# Callisto_Teknic_MSO_PBx4_v1p0.net
KiCad netlist of a schematic drawn in EAGLE
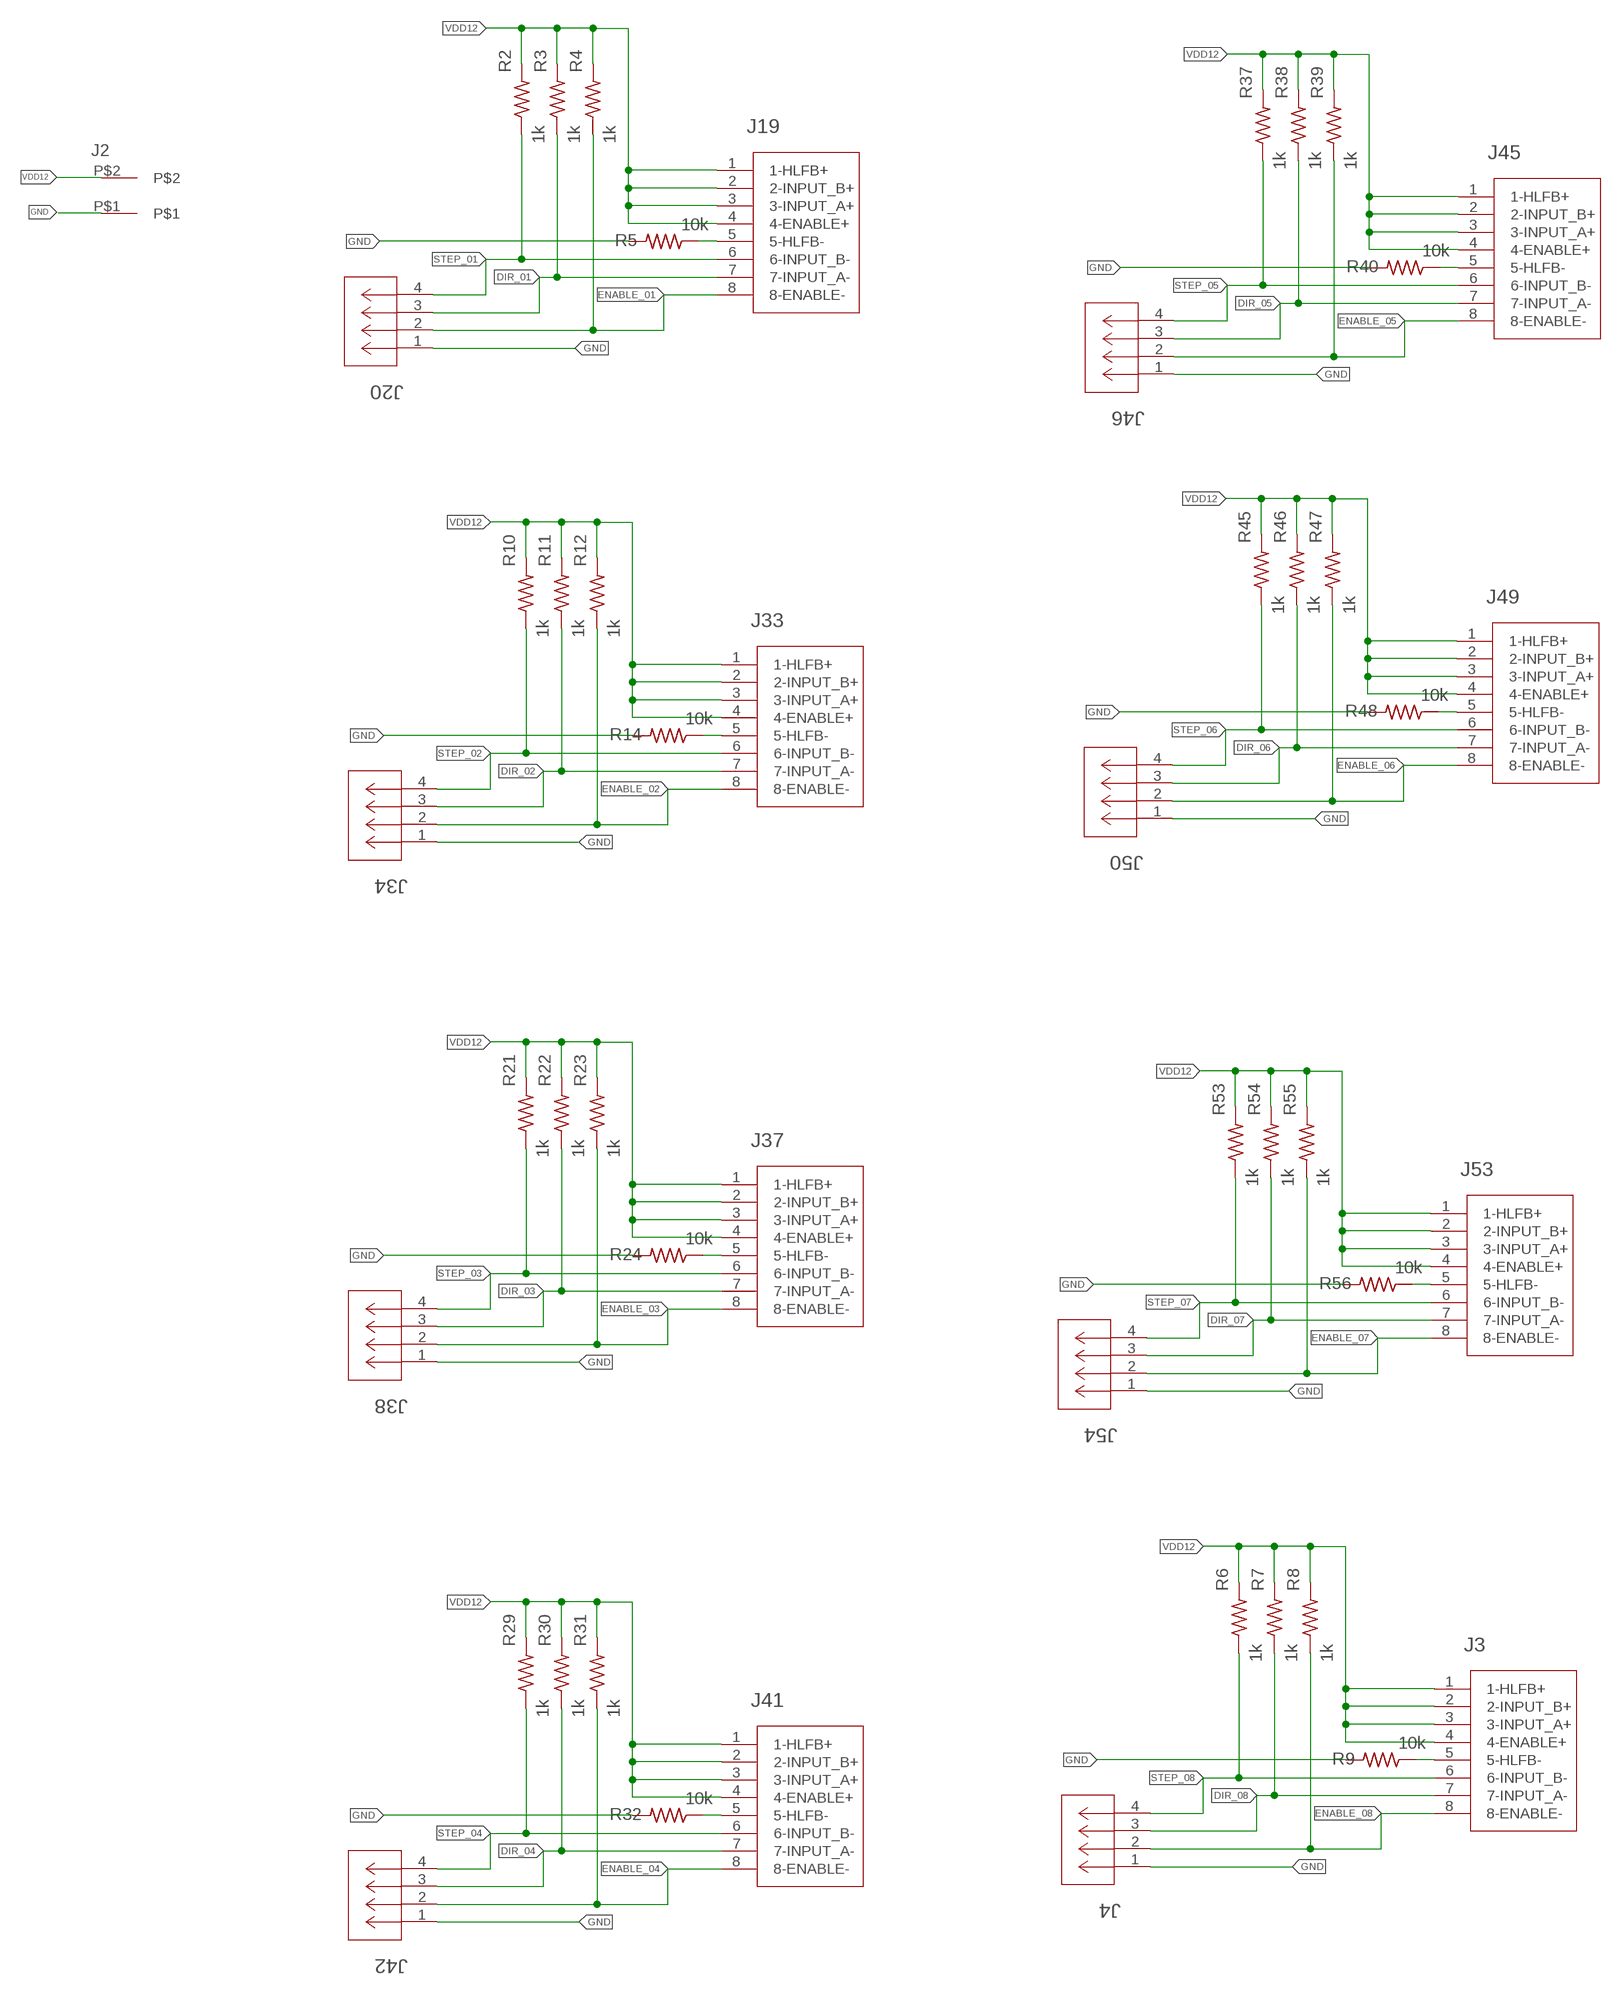
[diagram p0: schematic, sheet 1]

(export (version "E")
  (design (tool "Eeschema 10.0.6"))
  (components
    (comp (ref "J2")
      (value "2-pos")
      (footprint "eagle-import:2_3.81MM_PITCH")
      (fields (field (name "PARTNO") "691322310002"))
      (libsource (lib "eagle-import") (part "3.81MM_1_X_2_RT_ANGLE_PLUG_HEADER"))
    )
    (comp (ref "J3")
      (value "TEKNIC_8PIN_MOTOR")
      (footprint "eagle-import:CON_39281083")
      (fields
        (field (name "MANUFACTURER_PART_NUMBER") "39281083")
        (field (name "COPYRIGHT") "Copyright (C) 2022 Ultra Librarian. All rights reserved.")
      )
      (libsource (lib "eagle-import") (part "TEKNIC_8PIN_MOTOR"))
    )
    (comp (ref "J4")
      (value "CONN_530470410_PICOBLADE_X_4")
      (footprint "eagle-import:CON_530470410_MOL")
      (fields
        (field (name "MANUFACTURER_PART_NUMBER") "530470410")
        (field (name "COPYRIGHT") "Copyright (C) 2022 Ultra Librarian. All rights reserved.")
      )
      (libsource (lib "eagle-import") (part "CONN_530470410_PICOBLADE_X_4"))
    )
    (comp (ref "J19")
      (value "TEKNIC_8PIN_MOTOR")
      (footprint "eagle-import:CON_39281083")
      (fields
        (field (name "MANUFACTURER_PART_NUMBER") "39281083")
        (field (name "COPYRIGHT") "Copyright (C) 2022 Ultra Librarian. All rights reserved.")
      )
      (libsource (lib "eagle-import") (part "TEKNIC_8PIN_MOTOR"))
    )
    (comp (ref "J20")
      (value "CONN_530470410_PICOBLADE_X_4")
      (footprint "eagle-import:CON_530470410_MOL")
      (fields
        (field (name "MANUFACTURER_PART_NUMBER") "530470410")
        (field (name "COPYRIGHT") "Copyright (C) 2022 Ultra Librarian. All rights reserved.")
      )
      (libsource (lib "eagle-import") (part "CONN_530470410_PICOBLADE_X_4"))
    )
    (comp (ref "J33")
      (value "TEKNIC_8PIN_MOTOR")
      (footprint "eagle-import:CON_39281083")
      (fields
        (field (name "MANUFACTURER_PART_NUMBER") "39281083")
        (field (name "COPYRIGHT") "Copyright (C) 2022 Ultra Librarian. All rights reserved.")
      )
      (libsource (lib "eagle-import") (part "TEKNIC_8PIN_MOTOR"))
    )
    (comp (ref "J34")
      (value "CONN_530470410_PICOBLADE_X_4")
      (footprint "eagle-import:CON_530470410_MOL")
      (fields
        (field (name "MANUFACTURER_PART_NUMBER") "530470410")
        (field (name "COPYRIGHT") "Copyright (C) 2022 Ultra Librarian. All rights reserved.")
      )
      (libsource (lib "eagle-import") (part "CONN_530470410_PICOBLADE_X_4"))
    )
    (comp (ref "J37")
      (value "TEKNIC_8PIN_MOTOR")
      (footprint "eagle-import:CON_39281083")
      (fields
        (field (name "MANUFACTURER_PART_NUMBER") "39281083")
        (field (name "COPYRIGHT") "Copyright (C) 2022 Ultra Librarian. All rights reserved.")
      )
      (libsource (lib "eagle-import") (part "TEKNIC_8PIN_MOTOR"))
    )
    (comp (ref "J38")
      (value "CONN_530470410_PICOBLADE_X_4")
      (footprint "eagle-import:CON_530470410_MOL")
      (fields
        (field (name "MANUFACTURER_PART_NUMBER") "530470410")
        (field (name "COPYRIGHT") "Copyright (C) 2022 Ultra Librarian. All rights reserved.")
      )
      (libsource (lib "eagle-import") (part "CONN_530470410_PICOBLADE_X_4"))
    )
    (comp (ref "J41")
      (value "TEKNIC_8PIN_MOTOR")
      (footprint "eagle-import:CON_39281083")
      (fields
        (field (name "MANUFACTURER_PART_NUMBER") "39281083")
        (field (name "COPYRIGHT") "Copyright (C) 2022 Ultra Librarian. All rights reserved.")
      )
      (libsource (lib "eagle-import") (part "TEKNIC_8PIN_MOTOR"))
    )
    (comp (ref "J42")
      (value "CONN_530470410_PICOBLADE_X_4")
      (footprint "eagle-import:CON_530470410_MOL")
      (fields
        (field (name "MANUFACTURER_PART_NUMBER") "530470410")
        (field (name "COPYRIGHT") "Copyright (C) 2022 Ultra Librarian. All rights reserved.")
      )
      (libsource (lib "eagle-import") (part "CONN_530470410_PICOBLADE_X_4"))
    )
    (comp (ref "J45")
      (value "TEKNIC_8PIN_MOTOR")
      (footprint "eagle-import:CON_39281083")
      (fields
        (field (name "MANUFACTURER_PART_NUMBER") "39281083")
        (field (name "COPYRIGHT") "Copyright (C) 2022 Ultra Librarian. All rights reserved.")
      )
      (libsource (lib "eagle-import") (part "TEKNIC_8PIN_MOTOR"))
    )
    (comp (ref "J46")
      (value "CONN_530470410_PICOBLADE_X_4")
      (footprint "eagle-import:CON_530470410_MOL")
      (fields
        (field (name "MANUFACTURER_PART_NUMBER") "530470410")
        (field (name "COPYRIGHT") "Copyright (C) 2022 Ultra Librarian. All rights reserved.")
      )
      (libsource (lib "eagle-import") (part "CONN_530470410_PICOBLADE_X_4"))
    )
    (comp (ref "J49")
      (value "TEKNIC_8PIN_MOTOR")
      (footprint "eagle-import:CON_39281083")
      (fields
        (field (name "MANUFACTURER_PART_NUMBER") "39281083")
        (field (name "COPYRIGHT") "Copyright (C) 2022 Ultra Librarian. All rights reserved.")
      )
      (libsource (lib "eagle-import") (part "TEKNIC_8PIN_MOTOR"))
    )
    (comp (ref "J50")
      (value "CONN_530470410_PICOBLADE_X_4")
      (footprint "eagle-import:CON_530470410_MOL")
      (fields
        (field (name "MANUFACTURER_PART_NUMBER") "530470410")
        (field (name "COPYRIGHT") "Copyright (C) 2022 Ultra Librarian. All rights reserved.")
      )
      (libsource (lib "eagle-import") (part "CONN_530470410_PICOBLADE_X_4"))
    )
    (comp (ref "J53")
      (value "TEKNIC_8PIN_MOTOR")
      (footprint "eagle-import:CON_39281083")
      (fields
        (field (name "MANUFACTURER_PART_NUMBER") "39281083")
        (field (name "COPYRIGHT") "Copyright (C) 2022 Ultra Librarian. All rights reserved.")
      )
      (libsource (lib "eagle-import") (part "TEKNIC_8PIN_MOTOR"))
    )
    (comp (ref "J54")
      (value "CONN_530470410_PICOBLADE_X_4")
      (footprint "eagle-import:CON_530470410_MOL")
      (fields
        (field (name "MANUFACTURER_PART_NUMBER") "530470410")
        (field (name "COPYRIGHT") "Copyright (C) 2022 Ultra Librarian. All rights reserved.")
      )
      (libsource (lib "eagle-import") (part "CONN_530470410_PICOBLADE_X_4"))
    )
    (comp (ref "R2")
      (value "1k")
      (footprint "eagle-import:0805")
      (libsource (lib "eagle-import") (part "R_0805"))
    )
    (comp (ref "R3")
      (value "1k")
      (footprint "eagle-import:0805")
      (libsource (lib "eagle-import") (part "R_0805"))
    )
    (comp (ref "R4")
      (value "1k")
      (footprint "eagle-import:0805")
      (libsource (lib "eagle-import") (part "R_0805"))
    )
    (comp (ref "R5")
      (value "10k")
      (footprint "eagle-import:0805")
      (libsource (lib "eagle-import") (part "R_0805"))
    )
    (comp (ref "R6")
      (value "1k")
      (footprint "eagle-import:0805")
      (libsource (lib "eagle-import") (part "R_0805"))
    )
    (comp (ref "R7")
      (value "1k")
      (footprint "eagle-import:0805")
      (libsource (lib "eagle-import") (part "R_0805"))
    )
    (comp (ref "R8")
      (value "1k")
      (footprint "eagle-import:0805")
      (libsource (lib "eagle-import") (part "R_0805"))
    )
    (comp (ref "R9")
      (value "10k")
      (footprint "eagle-import:0805")
      (libsource (lib "eagle-import") (part "R_0805"))
    )
    (comp (ref "R10")
      (value "1k")
      (footprint "eagle-import:0805")
      (libsource (lib "eagle-import") (part "R_0805"))
    )
    (comp (ref "R11")
      (value "1k")
      (footprint "eagle-import:0805")
      (libsource (lib "eagle-import") (part "R_0805"))
    )
    (comp (ref "R12")
      (value "1k")
      (footprint "eagle-import:0805")
      (libsource (lib "eagle-import") (part "R_0805"))
    )
    (comp (ref "R14")
      (value "10k")
      (footprint "eagle-import:0805")
      (libsource (lib "eagle-import") (part "R_0805"))
    )
    (comp (ref "R21")
      (value "1k")
      (footprint "eagle-import:0805")
      (libsource (lib "eagle-import") (part "R_0805"))
    )
    (comp (ref "R22")
      (value "1k")
      (footprint "eagle-import:0805")
      (libsource (lib "eagle-import") (part "R_0805"))
    )
    (comp (ref "R23")
      (value "1k")
      (footprint "eagle-import:0805")
      (libsource (lib "eagle-import") (part "R_0805"))
    )
    (comp (ref "R24")
      (value "10k")
      (footprint "eagle-import:0805")
      (libsource (lib "eagle-import") (part "R_0805"))
    )
    (comp (ref "R29")
      (value "1k")
      (footprint "eagle-import:0805")
      (libsource (lib "eagle-import") (part "R_0805"))
    )
    (comp (ref "R30")
      (value "1k")
      (footprint "eagle-import:0805")
      (libsource (lib "eagle-import") (part "R_0805"))
    )
    (comp (ref "R31")
      (value "1k")
      (footprint "eagle-import:0805")
      (libsource (lib "eagle-import") (part "R_0805"))
    )
    (comp (ref "R32")
      (value "10k")
      (footprint "eagle-import:0805")
      (libsource (lib "eagle-import") (part "R_0805"))
    )
    (comp (ref "R37")
      (value "1k")
      (footprint "eagle-import:0805")
      (libsource (lib "eagle-import") (part "R_0805"))
    )
    (comp (ref "R38")
      (value "1k")
      (footprint "eagle-import:0805")
      (libsource (lib "eagle-import") (part "R_0805"))
    )
    (comp (ref "R39")
      (value "1k")
      (footprint "eagle-import:0805")
      (libsource (lib "eagle-import") (part "R_0805"))
    )
    (comp (ref "R40")
      (value "10k")
      (footprint "eagle-import:0805")
      (libsource (lib "eagle-import") (part "R_0805"))
    )
    (comp (ref "R45")
      (value "1k")
      (footprint "eagle-import:0805")
      (libsource (lib "eagle-import") (part "R_0805"))
    )
    (comp (ref "R46")
      (value "1k")
      (footprint "eagle-import:0805")
      (libsource (lib "eagle-import") (part "R_0805"))
    )
    (comp (ref "R47")
      (value "1k")
      (footprint "eagle-import:0805")
      (libsource (lib "eagle-import") (part "R_0805"))
    )
    (comp (ref "R48")
      (value "10k")
      (footprint "eagle-import:0805")
      (libsource (lib "eagle-import") (part "R_0805"))
    )
    (comp (ref "R53")
      (value "1k")
      (footprint "eagle-import:0805")
      (libsource (lib "eagle-import") (part "R_0805"))
    )
    (comp (ref "R54")
      (value "1k")
      (footprint "eagle-import:0805")
      (libsource (lib "eagle-import") (part "R_0805"))
    )
    (comp (ref "R55")
      (value "1k")
      (footprint "eagle-import:0805")
      (libsource (lib "eagle-import") (part "R_0805"))
    )
    (comp (ref "R56")
      (value "10k")
      (footprint "eagle-import:0805")
      (libsource (lib "eagle-import") (part "R_0805"))
    )
  )
  (nets
    (net (code "1") (name "DIR_01") (class "Default")
      (node (ref "J19") (pin "7") (pinfunction "7-INPUT_A-_7") (pintype "passive"))
      (node (ref "J20") (pin "3") (pinfunction "3_3") (pintype "passive"))
      (node (ref "R3") (pin "1") (pinfunction "1_1") (pintype "passive"))
    )
    (net (code "2") (name "DIR_02") (class "Default")
      (node (ref "J33") (pin "7") (pinfunction "7-INPUT_A-_7") (pintype "passive"))
      (node (ref "J34") (pin "3") (pinfunction "3_3") (pintype "passive"))
      (node (ref "R11") (pin "1") (pinfunction "1_1") (pintype "passive"))
    )
    (net (code "3") (name "DIR_03") (class "Default")
      (node (ref "J37") (pin "7") (pinfunction "7-INPUT_A-_7") (pintype "passive"))
      (node (ref "J38") (pin "3") (pinfunction "3_3") (pintype "passive"))
      (node (ref "R22") (pin "1") (pinfunction "1_1") (pintype "passive"))
    )
    (net (code "4") (name "DIR_04") (class "Default")
      (node (ref "J41") (pin "7") (pinfunction "7-INPUT_A-_7") (pintype "passive"))
      (node (ref "J42") (pin "3") (pinfunction "3_3") (pintype "passive"))
      (node (ref "R30") (pin "1") (pinfunction "1_1") (pintype "passive"))
    )
    (net (code "5") (name "DIR_05") (class "Default")
      (node (ref "J45") (pin "7") (pinfunction "7-INPUT_A-_7") (pintype "passive"))
      (node (ref "J46") (pin "3") (pinfunction "3_3") (pintype "passive"))
      (node (ref "R38") (pin "1") (pinfunction "1_1") (pintype "passive"))
    )
    (net (code "6") (name "DIR_06") (class "Default")
      (node (ref "J49") (pin "7") (pinfunction "7-INPUT_A-_7") (pintype "passive"))
      (node (ref "J50") (pin "3") (pinfunction "3_3") (pintype "passive"))
      (node (ref "R46") (pin "1") (pinfunction "1_1") (pintype "passive"))
    )
    (net (code "7") (name "DIR_07") (class "Default")
      (node (ref "J53") (pin "7") (pinfunction "7-INPUT_A-_7") (pintype "passive"))
      (node (ref "J54") (pin "3") (pinfunction "3_3") (pintype "passive"))
      (node (ref "R54") (pin "1") (pinfunction "1_1") (pintype "passive"))
    )
    (net (code "8") (name "DIR_08") (class "Default")
      (node (ref "J3") (pin "7") (pinfunction "7-INPUT_A-_7") (pintype "passive"))
      (node (ref "J4") (pin "3") (pinfunction "3_3") (pintype "passive"))
      (node (ref "R7") (pin "1") (pinfunction "1_1") (pintype "passive"))
    )
    (net (code "9") (name "ENABLE_01") (class "Default")
      (node (ref "J19") (pin "8") (pinfunction "8-ENABLE-_8") (pintype "passive"))
      (node (ref "J20") (pin "2") (pinfunction "2_2") (pintype "passive"))
      (node (ref "R4") (pin "1") (pinfunction "1_1") (pintype "passive"))
    )
    (net (code "10") (name "ENABLE_02") (class "Default")
      (node (ref "J33") (pin "8") (pinfunction "8-ENABLE-_8") (pintype "passive"))
      (node (ref "J34") (pin "2") (pinfunction "2_2") (pintype "passive"))
      (node (ref "R12") (pin "1") (pinfunction "1_1") (pintype "passive"))
    )
    (net (code "11") (name "ENABLE_03") (class "Default")
      (node (ref "J37") (pin "8") (pinfunction "8-ENABLE-_8") (pintype "passive"))
      (node (ref "J38") (pin "2") (pinfunction "2_2") (pintype "passive"))
      (node (ref "R23") (pin "1") (pinfunction "1_1") (pintype "passive"))
    )
    (net (code "12") (name "ENABLE_04") (class "Default")
      (node (ref "J41") (pin "8") (pinfunction "8-ENABLE-_8") (pintype "passive"))
      (node (ref "J42") (pin "2") (pinfunction "2_2") (pintype "passive"))
      (node (ref "R31") (pin "1") (pinfunction "1_1") (pintype "passive"))
    )
    (net (code "13") (name "ENABLE_05") (class "Default")
      (node (ref "J45") (pin "8") (pinfunction "8-ENABLE-_8") (pintype "passive"))
      (node (ref "J46") (pin "2") (pinfunction "2_2") (pintype "passive"))
      (node (ref "R39") (pin "1") (pinfunction "1_1") (pintype "passive"))
    )
    (net (code "14") (name "ENABLE_06") (class "Default")
      (node (ref "J49") (pin "8") (pinfunction "8-ENABLE-_8") (pintype "passive"))
      (node (ref "J50") (pin "2") (pinfunction "2_2") (pintype "passive"))
      (node (ref "R47") (pin "1") (pinfunction "1_1") (pintype "passive"))
    )
    (net (code "15") (name "ENABLE_07") (class "Default")
      (node (ref "J53") (pin "8") (pinfunction "8-ENABLE-_8") (pintype "passive"))
      (node (ref "J54") (pin "2") (pinfunction "2_2") (pintype "passive"))
      (node (ref "R55") (pin "1") (pinfunction "1_1") (pintype "passive"))
    )
    (net (code "16") (name "ENABLE_08") (class "Default")
      (node (ref "J3") (pin "8") (pinfunction "8-ENABLE-_8") (pintype "passive"))
      (node (ref "J4") (pin "2") (pinfunction "2_2") (pintype "passive"))
      (node (ref "R8") (pin "1") (pinfunction "1_1") (pintype "passive"))
    )
    (net (code "17") (name "GND") (class "Default")
      (node (ref "J2") (pin "P$1") (pinfunction "P$1_P$1") (pintype "bidirectional"))
      (node (ref "J20") (pin "1") (pinfunction "1_1") (pintype "passive"))
      (node (ref "J34") (pin "1") (pinfunction "1_1") (pintype "passive"))
      (node (ref "J38") (pin "1") (pinfunction "1_1") (pintype "passive"))
      (node (ref "J4") (pin "1") (pinfunction "1_1") (pintype "passive"))
      (node (ref "J42") (pin "1") (pinfunction "1_1") (pintype "passive"))
      (node (ref "J46") (pin "1") (pinfunction "1_1") (pintype "passive"))
      (node (ref "J50") (pin "1") (pinfunction "1_1") (pintype "passive"))
      (node (ref "J54") (pin "1") (pinfunction "1_1") (pintype "passive"))
      (node (ref "R14") (pin "2") (pinfunction "2_2") (pintype "passive"))
      (node (ref "R24") (pin "2") (pinfunction "2_2") (pintype "passive"))
      (node (ref "R32") (pin "2") (pinfunction "2_2") (pintype "passive"))
      (node (ref "R40") (pin "2") (pinfunction "2_2") (pintype "passive"))
      (node (ref "R48") (pin "2") (pinfunction "2_2") (pintype "passive"))
      (node (ref "R5") (pin "2") (pinfunction "2_2") (pintype "passive"))
      (node (ref "R56") (pin "2") (pinfunction "2_2") (pintype "passive"))
      (node (ref "R9") (pin "2") (pinfunction "2_2") (pintype "passive"))
    )
    (net (code "18") (name "Net-(J3-5-HLFB-)") (class "Default")
      (node (ref "J3") (pin "5") (pinfunction "5-HLFB-_5") (pintype "passive"))
      (node (ref "R9") (pin "1") (pinfunction "1_1") (pintype "passive"))
    )
    (net (code "19") (name "Net-(J19-5-HLFB-)") (class "Default")
      (node (ref "J19") (pin "5") (pinfunction "5-HLFB-_5") (pintype "passive"))
      (node (ref "R5") (pin "1") (pinfunction "1_1") (pintype "passive"))
    )
    (net (code "20") (name "Net-(J33-5-HLFB-)") (class "Default")
      (node (ref "J33") (pin "5") (pinfunction "5-HLFB-_5") (pintype "passive"))
      (node (ref "R14") (pin "1") (pinfunction "1_1") (pintype "passive"))
    )
    (net (code "21") (name "Net-(J37-5-HLFB-)") (class "Default")
      (node (ref "J37") (pin "5") (pinfunction "5-HLFB-_5") (pintype "passive"))
      (node (ref "R24") (pin "1") (pinfunction "1_1") (pintype "passive"))
    )
    (net (code "22") (name "Net-(J41-5-HLFB-)") (class "Default")
      (node (ref "J41") (pin "5") (pinfunction "5-HLFB-_5") (pintype "passive"))
      (node (ref "R32") (pin "1") (pinfunction "1_1") (pintype "passive"))
    )
    (net (code "23") (name "Net-(J45-5-HLFB-)") (class "Default")
      (node (ref "J45") (pin "5") (pinfunction "5-HLFB-_5") (pintype "passive"))
      (node (ref "R40") (pin "1") (pinfunction "1_1") (pintype "passive"))
    )
    (net (code "24") (name "Net-(J49-5-HLFB-)") (class "Default")
      (node (ref "J49") (pin "5") (pinfunction "5-HLFB-_5") (pintype "passive"))
      (node (ref "R48") (pin "1") (pinfunction "1_1") (pintype "passive"))
    )
    (net (code "25") (name "Net-(J53-5-HLFB-)") (class "Default")
      (node (ref "J53") (pin "5") (pinfunction "5-HLFB-_5") (pintype "passive"))
      (node (ref "R56") (pin "1") (pinfunction "1_1") (pintype "passive"))
    )
    (net (code "26") (name "STEP_01") (class "Default")
      (node (ref "J19") (pin "6") (pinfunction "6-INPUT_B-_6") (pintype "passive"))
      (node (ref "J20") (pin "4") (pinfunction "4_4") (pintype "passive"))
      (node (ref "R2") (pin "1") (pinfunction "1_1") (pintype "passive"))
    )
    (net (code "27") (name "STEP_02") (class "Default")
      (node (ref "J33") (pin "6") (pinfunction "6-INPUT_B-_6") (pintype "passive"))
      (node (ref "J34") (pin "4") (pinfunction "4_4") (pintype "passive"))
      (node (ref "R10") (pin "1") (pinfunction "1_1") (pintype "passive"))
    )
    (net (code "28") (name "STEP_03") (class "Default")
      (node (ref "J37") (pin "6") (pinfunction "6-INPUT_B-_6") (pintype "passive"))
      (node (ref "J38") (pin "4") (pinfunction "4_4") (pintype "passive"))
      (node (ref "R21") (pin "1") (pinfunction "1_1") (pintype "passive"))
    )
    (net (code "29") (name "STEP_04") (class "Default")
      (node (ref "J41") (pin "6") (pinfunction "6-INPUT_B-_6") (pintype "passive"))
      (node (ref "J42") (pin "4") (pinfunction "4_4") (pintype "passive"))
      (node (ref "R29") (pin "1") (pinfunction "1_1") (pintype "passive"))
    )
    (net (code "30") (name "STEP_05") (class "Default")
      (node (ref "J45") (pin "6") (pinfunction "6-INPUT_B-_6") (pintype "passive"))
      (node (ref "J46") (pin "4") (pinfunction "4_4") (pintype "passive"))
      (node (ref "R37") (pin "1") (pinfunction "1_1") (pintype "passive"))
    )
    (net (code "31") (name "STEP_06") (class "Default")
      (node (ref "J49") (pin "6") (pinfunction "6-INPUT_B-_6") (pintype "passive"))
      (node (ref "J50") (pin "4") (pinfunction "4_4") (pintype "passive"))
      (node (ref "R45") (pin "1") (pinfunction "1_1") (pintype "passive"))
    )
    (net (code "32") (name "STEP_07") (class "Default")
      (node (ref "J53") (pin "6") (pinfunction "6-INPUT_B-_6") (pintype "passive"))
      (node (ref "J54") (pin "4") (pinfunction "4_4") (pintype "passive"))
      (node (ref "R53") (pin "1") (pinfunction "1_1") (pintype "passive"))
    )
    (net (code "33") (name "STEP_08") (class "Default")
      (node (ref "J3") (pin "6") (pinfunction "6-INPUT_B-_6") (pintype "passive"))
      (node (ref "J4") (pin "4") (pinfunction "4_4") (pintype "passive"))
      (node (ref "R6") (pin "1") (pinfunction "1_1") (pintype "passive"))
    )
    (net (code "34") (name "VDD12") (class "Default")
      (node (ref "J19") (pin "1") (pinfunction "1-HLFB+_1") (pintype "passive"))
      (node (ref "J19") (pin "2") (pinfunction "2-INPUT_B+_2") (pintype "passive"))
      (node (ref "J19") (pin "3") (pinfunction "3-INPUT_A+_3") (pintype "passive"))
      (node (ref "J19") (pin "4") (pinfunction "4-ENABLE+_4") (pintype "passive"))
      (node (ref "J2") (pin "P$2") (pinfunction "P$2_P$2") (pintype "bidirectional"))
      (node (ref "J3") (pin "1") (pinfunction "1-HLFB+_1") (pintype "passive"))
      (node (ref "J3") (pin "2") (pinfunction "2-INPUT_B+_2") (pintype "passive"))
      (node (ref "J3") (pin "3") (pinfunction "3-INPUT_A+_3") (pintype "passive"))
      (node (ref "J3") (pin "4") (pinfunction "4-ENABLE+_4") (pintype "passive"))
      (node (ref "J33") (pin "1") (pinfunction "1-HLFB+_1") (pintype "passive"))
      (node (ref "J33") (pin "2") (pinfunction "2-INPUT_B+_2") (pintype "passive"))
      (node (ref "J33") (pin "3") (pinfunction "3-INPUT_A+_3") (pintype "passive"))
      (node (ref "J33") (pin "4") (pinfunction "4-ENABLE+_4") (pintype "passive"))
      (node (ref "J37") (pin "1") (pinfunction "1-HLFB+_1") (pintype "passive"))
      (node (ref "J37") (pin "2") (pinfunction "2-INPUT_B+_2") (pintype "passive"))
      (node (ref "J37") (pin "3") (pinfunction "3-INPUT_A+_3") (pintype "passive"))
      (node (ref "J37") (pin "4") (pinfunction "4-ENABLE+_4") (pintype "passive"))
      (node (ref "J41") (pin "1") (pinfunction "1-HLFB+_1") (pintype "passive"))
      (node (ref "J41") (pin "2") (pinfunction "2-INPUT_B+_2") (pintype "passive"))
      (node (ref "J41") (pin "3") (pinfunction "3-INPUT_A+_3") (pintype "passive"))
      (node (ref "J41") (pin "4") (pinfunction "4-ENABLE+_4") (pintype "passive"))
      (node (ref "J45") (pin "1") (pinfunction "1-HLFB+_1") (pintype "passive"))
      (node (ref "J45") (pin "2") (pinfunction "2-INPUT_B+_2") (pintype "passive"))
      (node (ref "J45") (pin "3") (pinfunction "3-INPUT_A+_3") (pintype "passive"))
      (node (ref "J45") (pin "4") (pinfunction "4-ENABLE+_4") (pintype "passive"))
      (node (ref "J49") (pin "1") (pinfunction "1-HLFB+_1") (pintype "passive"))
      (node (ref "J49") (pin "2") (pinfunction "2-INPUT_B+_2") (pintype "passive"))
      (node (ref "J49") (pin "3") (pinfunction "3-INPUT_A+_3") (pintype "passive"))
      (node (ref "J49") (pin "4") (pinfunction "4-ENABLE+_4") (pintype "passive"))
      (node (ref "J53") (pin "1") (pinfunction "1-HLFB+_1") (pintype "passive"))
      (node (ref "J53") (pin "2") (pinfunction "2-INPUT_B+_2") (pintype "passive"))
      (node (ref "J53") (pin "3") (pinfunction "3-INPUT_A+_3") (pintype "passive"))
      (node (ref "J53") (pin "4") (pinfunction "4-ENABLE+_4") (pintype "passive"))
      (node (ref "R10") (pin "2") (pinfunction "2_2") (pintype "passive"))
      (node (ref "R11") (pin "2") (pinfunction "2_2") (pintype "passive"))
      (node (ref "R12") (pin "2") (pinfunction "2_2") (pintype "passive"))
      (node (ref "R2") (pin "2") (pinfunction "2_2") (pintype "passive"))
      (node (ref "R21") (pin "2") (pinfunction "2_2") (pintype "passive"))
      (node (ref "R22") (pin "2") (pinfunction "2_2") (pintype "passive"))
      (node (ref "R23") (pin "2") (pinfunction "2_2") (pintype "passive"))
      (node (ref "R29") (pin "2") (pinfunction "2_2") (pintype "passive"))
      (node (ref "R3") (pin "2") (pinfunction "2_2") (pintype "passive"))
      (node (ref "R30") (pin "2") (pinfunction "2_2") (pintype "passive"))
      (node (ref "R31") (pin "2") (pinfunction "2_2") (pintype "passive"))
      (node (ref "R37") (pin "2") (pinfunction "2_2") (pintype "passive"))
      (node (ref "R38") (pin "2") (pinfunction "2_2") (pintype "passive"))
      (node (ref "R39") (pin "2") (pinfunction "2_2") (pintype "passive"))
      (node (ref "R4") (pin "2") (pinfunction "2_2") (pintype "passive"))
      (node (ref "R45") (pin "2") (pinfunction "2_2") (pintype "passive"))
      (node (ref "R46") (pin "2") (pinfunction "2_2") (pintype "passive"))
      (node (ref "R47") (pin "2") (pinfunction "2_2") (pintype "passive"))
      (node (ref "R53") (pin "2") (pinfunction "2_2") (pintype "passive"))
      (node (ref "R54") (pin "2") (pinfunction "2_2") (pintype "passive"))
      (node (ref "R55") (pin "2") (pinfunction "2_2") (pintype "passive"))
      (node (ref "R6") (pin "2") (pinfunction "2_2") (pintype "passive"))
      (node (ref "R7") (pin "2") (pinfunction "2_2") (pintype "passive"))
      (node (ref "R8") (pin "2") (pinfunction "2_2") (pintype "passive"))
    )
  )
)
